# bike-computer.net
KiCad netlist of a schematic drawn in EAGLE
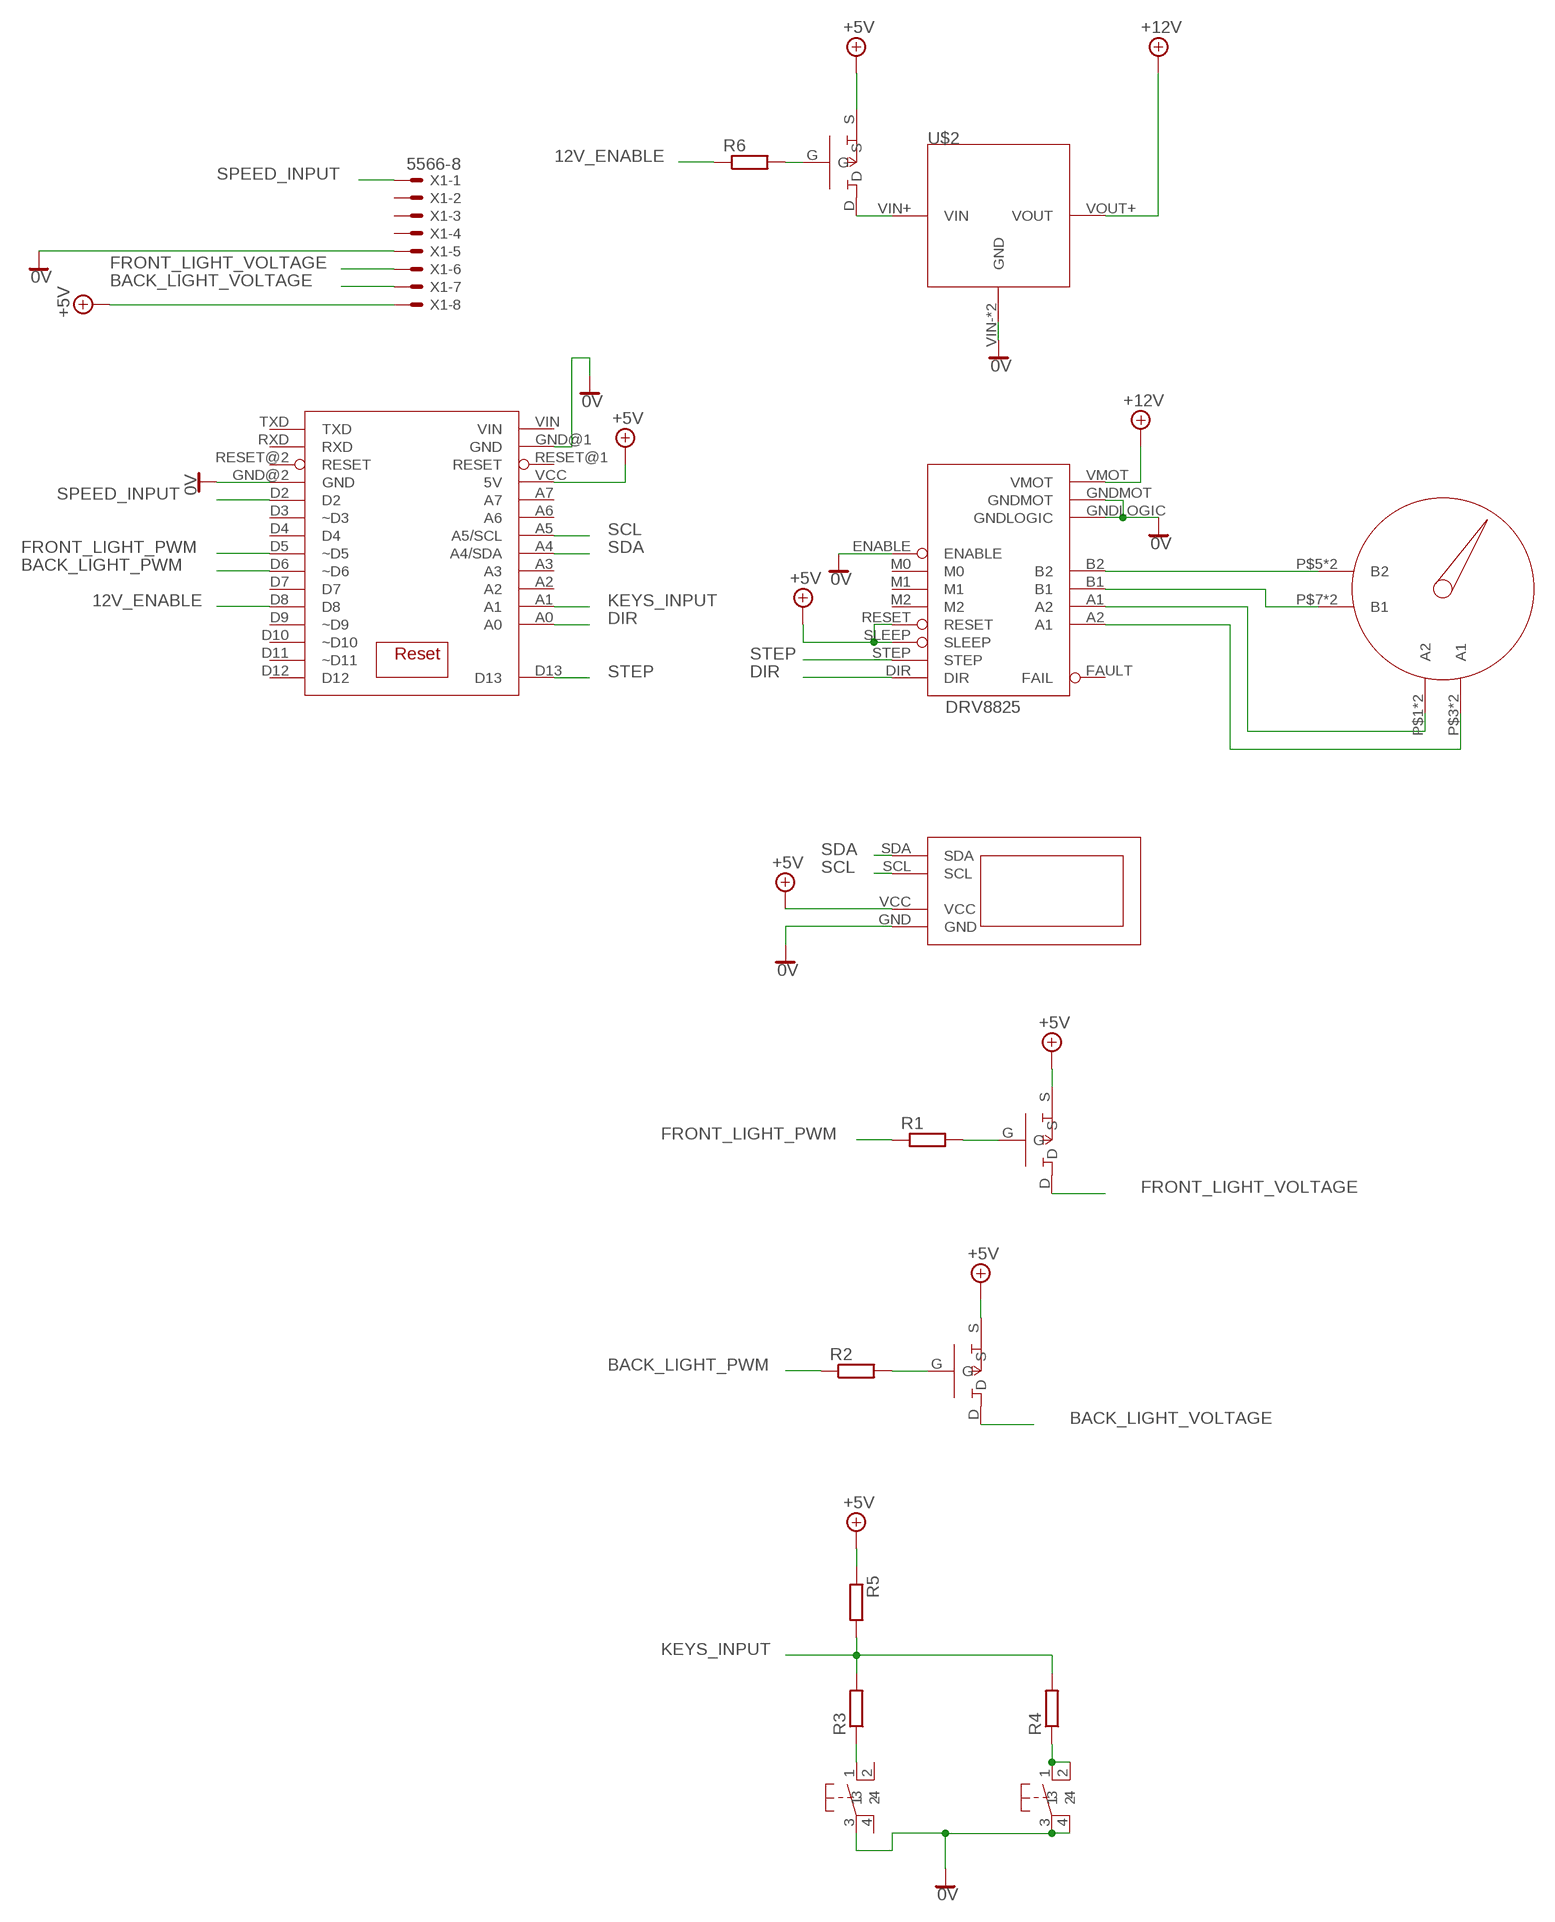
[diagram p0: schematic, sheet 1]

(export (version "E")
  (design (tool "Eeschema 10.0.6"))
  (components
    (comp (ref "DRV8825")
      (value "DRV8825_BOARD")
      (footprint "eagle-import:DRV8255_BOARD")
      (libsource (lib "eagle-import") (part "DRV8825_BOARD"))
    )
    (comp (ref "R1")
      (value "R-EU_0617/17")
      (footprint "eagle-import:0617_17")
      (libsource (lib "eagle-import") (part "R-EU_0617/17"))
    )
    (comp (ref "R2")
      (value "R-EU_0207/15")
      (footprint "eagle-import:0207_15")
      (libsource (lib "eagle-import") (part "R-EU_0207/15"))
    )
    (comp (ref "R3")
      (value "R-EU_0207/12")
      (footprint "eagle-import:0207_12")
      (libsource (lib "eagle-import") (part "R-EU_0207/12"))
    )
    (comp (ref "R4")
      (value "R-EU_0204/5")
      (footprint "eagle-import:0204_5")
      (libsource (lib "eagle-import") (part "R-EU_0204/5"))
    )
    (comp (ref "R5")
      (value "R-EU_0204/5")
      (footprint "eagle-import:0204_5")
      (libsource (lib "eagle-import") (part "R-EU_0204/5"))
    )
    (comp (ref "R6")
      (value "R-EU_0207/15")
      (footprint "eagle-import:0207_15")
      (libsource (lib "eagle-import") (part "R-EU_0207/15"))
    )
    (comp (ref "U$1")
      (value "STEPPER_GAUGE")
      (footprint "eagle-import:STEPPER_GAUGE")
      (libsource (lib "eagle-import") (part "STEPPER_GAUGE"))
    )
    (comp (ref "U$2")
      (value "STEP_UP_REG")
      (footprint "eagle-import:STEP_UP_REG")
      (libsource (lib "eagle-import") (part "STEP_UP_REG"))
    )
    (comp (ref "U$3")
      (value "OLED_0.9")
      (footprint "eagle-import:OLED_0.9")
      (libsource (lib "eagle-import") (part "OLED_0.9"))
    )
    (comp (ref "U$4")
      (value "BS250")
      (footprint "eagle-import:TO92(2.54)")
      (libsource (lib "eagle-import") (part "BS250"))
    )
    (comp (ref "U$5")
      (value "BS250")
      (footprint "eagle-import:TO92(2.54)")
      (libsource (lib "eagle-import") (part "BS250"))
    )
    (comp (ref "U$6")
      (value "BS250")
      (footprint "eagle-import:TO92(2.54)")
      (libsource (lib "eagle-import") (part "BS250"))
    )
    (comp (ref "U$7")
      (value "ARDUINO_PRO_MINI")
      (footprint "eagle-import:ARDUINO_PRO_MINI")
      (libsource (lib "eagle-import") (part "ARDUINO_PRO_MINI"))
    )
    (comp (ref "U$8")
      (value "MICRO_SWITCH")
      (footprint "eagle-import:MICRO_SWITCH")
      (libsource (lib "eagle-import") (part "MICRO_SWITCH"))
    )
    (comp (ref "U$9")
      (value "MICRO_SWITCH")
      (footprint "eagle-import:MICRO_SWITCH")
      (libsource (lib "eagle-import") (part "MICRO_SWITCH"))
    )
    (comp (ref "X1")
      (value "5566-8")
      (footprint "eagle-import:5566-8")
      (fields (field (name "MF") "MOLEX"))
      (libsource (lib "eagle-import") (part "5566-8"))
    )
  )
  (nets
    (net (code "1") (name "+5V") (class "Default")
      (node (ref "DRV8825") (pin "RESET") (pinfunction "RESET_RESET") (pintype "bidirectional"))
      (node (ref "DRV8825") (pin "SLEEP") (pinfunction "SLEEP_SLEEP") (pintype "bidirectional"))
      (node (ref "R5") (pin "1") (pinfunction "1_1") (pintype "passive"))
      (node (ref "U$3") (pin "VCC") (pinfunction "VCC_VCC") (pintype "bidirectional"))
      (node (ref "U$4") (pin "S") (pinfunction "S_S") (pintype "bidirectional"))
      (node (ref "U$5") (pin "S") (pinfunction "S_S") (pintype "bidirectional"))
      (node (ref "U$6") (pin "S") (pinfunction "S_S") (pintype "bidirectional"))
      (node (ref "U$7") (pin "VCC") (pinfunction "5V_VCC") (pintype "bidirectional"))
      (node (ref "X1") (pin "8") (pinfunction "S_8") (pintype "passive"))
    )
    (net (code "2") (name "+12V") (class "Default")
      (node (ref "DRV8825") (pin "VMOT") (pinfunction "VMOT_VMOT") (pintype "bidirectional"))
      (node (ref "U$2") (pin "VOUT+") (pinfunction "VOUT_VOUT+") (pintype "bidirectional"))
    )
    (net (code "3") (name "/12V_ENABLE") (class "Default")
      (node (ref "R6") (pin "1") (pinfunction "1_1") (pintype "passive"))
      (node (ref "U$7") (pin "D8") (pinfunction "D8_D8") (pintype "bidirectional"))
    )
    (net (code "4") (name "/BACK_LIGHT_PWM") (class "Default")
      (node (ref "R2") (pin "1") (pinfunction "1_1") (pintype "passive"))
      (node (ref "U$7") (pin "D6") (pinfunction "~{D6}_D6") (pintype "bidirectional"))
    )
    (net (code "5") (name "/BACK_LIGHT_VOLTAGE") (class "Default")
      (node (ref "U$5") (pin "D") (pinfunction "D_D") (pintype "bidirectional"))
      (node (ref "X1") (pin "7") (pinfunction "S_7") (pintype "passive"))
    )
    (net (code "6") (name "/DIR") (class "Default")
      (node (ref "DRV8825") (pin "DIR") (pinfunction "DIR_DIR") (pintype "bidirectional"))
      (node (ref "U$7") (pin "A0") (pinfunction "A0_A0") (pintype "bidirectional"))
    )
    (net (code "7") (name "/FRONT_LIGHT_PWM") (class "Default")
      (node (ref "R1") (pin "1") (pinfunction "1_1") (pintype "passive"))
      (node (ref "U$7") (pin "D5") (pinfunction "~{D5}_D5") (pintype "bidirectional"))
    )
    (net (code "8") (name "/FRONT_LIGHT_VOLTAGE") (class "Default")
      (node (ref "U$4") (pin "D") (pinfunction "D_D") (pintype "bidirectional"))
      (node (ref "X1") (pin "6") (pinfunction "S_6") (pintype "passive"))
    )
    (net (code "9") (name "/KEYS_INPUT") (class "Default")
      (node (ref "R3") (pin "2") (pinfunction "2_2") (pintype "passive"))
      (node (ref "R4") (pin "2") (pinfunction "2_2") (pintype "passive"))
      (node (ref "R5") (pin "2") (pinfunction "2_2") (pintype "passive"))
      (node (ref "U$7") (pin "A1") (pinfunction "A1_A1") (pintype "bidirectional"))
    )
    (net (code "10") (name "/SCL") (class "Default")
      (node (ref "U$3") (pin "SCL") (pinfunction "SCL_SCL") (pintype "bidirectional"))
      (node (ref "U$7") (pin "A5") (pinfunction "A5/SCL_A5") (pintype "bidirectional"))
    )
    (net (code "11") (name "/SDA") (class "Default")
      (node (ref "U$3") (pin "SDA") (pinfunction "SDA_SDA") (pintype "bidirectional"))
      (node (ref "U$7") (pin "A4") (pinfunction "A4/SDA_A4") (pintype "bidirectional"))
    )
    (net (code "12") (name "/SPEED_INPUT") (class "Default")
      (node (ref "U$7") (pin "D2") (pinfunction "D2_D2") (pintype "bidirectional"))
      (node (ref "X1") (pin "1") (pinfunction "S_1") (pintype "passive"))
    )
    (net (code "13") (name "/STEP") (class "Default")
      (node (ref "DRV8825") (pin "STEP") (pinfunction "STEP_STEP") (pintype "bidirectional"))
      (node (ref "U$7") (pin "D13") (pinfunction "D13_D13") (pintype "bidirectional"))
    )
    (net (code "14") (name "0V") (class "Default")
      (node (ref "DRV8825") (pin "ENABLE") (pinfunction "ENABLE_ENABLE") (pintype "bidirectional"))
      (node (ref "DRV8825") (pin "GNDLOGIC") (pinfunction "GNDLOGIC_GNDLOGIC") (pintype "bidirectional"))
      (node (ref "DRV8825") (pin "GNDMOT") (pinfunction "GNDMOT_GNDMOT") (pintype "bidirectional"))
      (node (ref "U$2") (pin "VIN-") (pinfunction "GND_VIN-") (pintype "bidirectional"))
      (node (ref "U$2") (pin "VOUT-") (pinfunction "GND_VOUT-") (pintype "bidirectional"))
      (node (ref "U$3") (pin "GND") (pinfunction "GND_GND") (pintype "bidirectional"))
      (node (ref "U$7") (pin "GND@1") (pinfunction "GND_GND@1") (pintype "bidirectional"))
      (node (ref "U$7") (pin "GND@2") (pinfunction "GND_GND@2") (pintype "bidirectional"))
      (node (ref "U$8") (pin "3") (pinfunction "3_3") (pintype "bidirectional"))
      (node (ref "U$9") (pin "3") (pinfunction "3_3") (pintype "bidirectional"))
      (node (ref "U$9") (pin "4") (pinfunction "4_4") (pintype "bidirectional"))
      (node (ref "X1") (pin "5") (pinfunction "S_5") (pintype "passive"))
    )
    (net (code "15") (name "Net-(DRV8825-A1)") (class "Default")
      (node (ref "DRV8825") (pin "A2") (pinfunction "A1_A2") (pintype "output"))
      (node (ref "U$1") (pin "P$3") (pinfunction "A1_P$3") (pintype "bidirectional"))
      (node (ref "U$1") (pin "P$4") (pinfunction "A1_P$4") (pintype "bidirectional"))
    )
    (net (code "16") (name "Net-(DRV8825-A2)") (class "Default")
      (node (ref "DRV8825") (pin "A1") (pinfunction "A2_A1") (pintype "output"))
      (node (ref "U$1") (pin "P$1") (pinfunction "A2_P$1") (pintype "bidirectional"))
      (node (ref "U$1") (pin "P$2") (pinfunction "A2_P$2") (pintype "bidirectional"))
    )
    (net (code "17") (name "Net-(DRV8825-PadB1)") (class "Default")
      (node (ref "DRV8825") (pin "B1") (pinfunction "B1_B1") (pintype "output"))
      (node (ref "U$1") (pin "P$7") (pinfunction "B1_P$7") (pintype "bidirectional"))
      (node (ref "U$1") (pin "P$8") (pinfunction "B1_P$8") (pintype "bidirectional"))
    )
    (net (code "18") (name "Net-(DRV8825-PadB2)") (class "Default")
      (node (ref "DRV8825") (pin "B2") (pinfunction "B2_B2") (pintype "output"))
      (node (ref "U$1") (pin "P$5") (pinfunction "B2_P$5") (pintype "bidirectional"))
      (node (ref "U$1") (pin "P$6") (pinfunction "B2_P$6") (pintype "bidirectional"))
    )
    (net (code "19") (name "Net-(R1-Pad2)") (class "Default")
      (node (ref "R1") (pin "2") (pinfunction "2_2") (pintype "passive"))
      (node (ref "U$4") (pin "G") (pinfunction "G_G") (pintype "bidirectional"))
    )
    (net (code "20") (name "Net-(R2-Pad2)") (class "Default")
      (node (ref "R2") (pin "2") (pinfunction "2_2") (pintype "passive"))
      (node (ref "U$5") (pin "G") (pinfunction "G_G") (pintype "bidirectional"))
    )
    (net (code "21") (name "Net-(R3-Pad1)") (class "Default")
      (node (ref "R3") (pin "1") (pinfunction "1_1") (pintype "passive"))
      (node (ref "U$8") (pin "1") (pinfunction "1_1") (pintype "bidirectional"))
    )
    (net (code "22") (name "Net-(R4-Pad1)") (class "Default")
      (node (ref "R4") (pin "1") (pinfunction "1_1") (pintype "passive"))
      (node (ref "U$9") (pin "1") (pinfunction "1_1") (pintype "bidirectional"))
      (node (ref "U$9") (pin "2") (pinfunction "2_2") (pintype "bidirectional"))
    )
    (net (code "23") (name "Net-(R6-Pad2)") (class "Default")
      (node (ref "R6") (pin "2") (pinfunction "2_2") (pintype "passive"))
      (node (ref "U$6") (pin "G") (pinfunction "G_G") (pintype "bidirectional"))
    )
    (net (code "24") (name "Net-(U$2-VIN)") (class "Default")
      (node (ref "U$2") (pin "VIN+") (pinfunction "VIN_VIN+") (pintype "bidirectional"))
      (node (ref "U$6") (pin "D") (pinfunction "D_D") (pintype "bidirectional"))
    )
    (net (code "25") (name "unconnected-(DRV8825-FAIL-PadFAULT)") (class "Default")
      (node (ref "DRV8825") (pin "FAULT") (pinfunction "FAIL_FAULT") (pintype "output"))
    )
    (net (code "26") (name "unconnected-(DRV8825-PadM0)") (class "Default")
      (node (ref "DRV8825") (pin "M0") (pinfunction "M0_M0") (pintype "input"))
    )
    (net (code "27") (name "unconnected-(DRV8825-PadM1)") (class "Default")
      (node (ref "DRV8825") (pin "M1") (pinfunction "M1_M1") (pintype "bidirectional"))
    )
    (net (code "28") (name "unconnected-(DRV8825-PadM2)") (class "Default")
      (node (ref "DRV8825") (pin "M2") (pinfunction "M2_M2") (pintype "bidirectional"))
    )
    (net (code "29") (name "unconnected-(U$7-PadA2)") (class "Default")
      (node (ref "U$7") (pin "A2") (pinfunction "A2_A2") (pintype "bidirectional"))
    )
    (net (code "30") (name "unconnected-(U$7-PadA3)") (class "Default")
      (node (ref "U$7") (pin "A3") (pinfunction "A3_A3") (pintype "bidirectional"))
    )
    (net (code "31") (name "unconnected-(U$7-PadA6)") (class "Default")
      (node (ref "U$7") (pin "A6") (pinfunction "A6_A6") (pintype "bidirectional"))
    )
    (net (code "32") (name "unconnected-(U$7-PadA7)") (class "Default")
      (node (ref "U$7") (pin "A7") (pinfunction "A7_A7") (pintype "bidirectional"))
    )
    (net (code "33") (name "unconnected-(U$7-PadD4)") (class "Default")
      (node (ref "U$7") (pin "D4") (pinfunction "D4_D4") (pintype "bidirectional"))
    )
    (net (code "34") (name "unconnected-(U$7-PadD7)") (class "Default")
      (node (ref "U$7") (pin "D7") (pinfunction "D7_D7") (pintype "bidirectional"))
    )
    (net (code "35") (name "unconnected-(U$7-PadD12)") (class "Default")
      (node (ref "U$7") (pin "D12") (pinfunction "D12_D12") (pintype "bidirectional"))
    )
    (net (code "36") (name "unconnected-(U$7-PadRXD)") (class "Default")
      (node (ref "U$7") (pin "RXD") (pinfunction "RXD_RXD") (pintype "bidirectional"))
    )
    (net (code "37") (name "unconnected-(U$7-PadTXD)") (class "Default")
      (node (ref "U$7") (pin "TXD") (pinfunction "TXD_TXD") (pintype "bidirectional"))
    )
    (net (code "38") (name "unconnected-(U$7-PadVIN)") (class "Default")
      (node (ref "U$7") (pin "VIN") (pinfunction "VIN_VIN") (pintype "bidirectional"))
    )
    (net (code "39") (name "unconnected-(U$7-RESET-PadRESET@1)") (class "Default")
      (node (ref "U$7") (pin "RESET@1") (pinfunction "RESET_RESET@1") (pintype "bidirectional"))
    )
    (net (code "40") (name "unconnected-(U$7-RESET-PadRESET@2)") (class "Default")
      (node (ref "U$7") (pin "RESET@2") (pinfunction "RESET_RESET@2") (pintype "bidirectional"))
    )
    (net (code "41") (name "unconnected-(U$7-~{D3}-PadD3)") (class "Default")
      (node (ref "U$7") (pin "D3") (pinfunction "~{D3}_D3") (pintype "bidirectional"))
    )
    (net (code "42") (name "unconnected-(U$7-~{D9}-PadD9)") (class "Default")
      (node (ref "U$7") (pin "D9") (pinfunction "~{D9}_D9") (pintype "bidirectional"))
    )
    (net (code "43") (name "unconnected-(U$7-~{D10}-PadD10)") (class "Default")
      (node (ref "U$7") (pin "D10") (pinfunction "~{D10}_D10") (pintype "bidirectional"))
    )
    (net (code "44") (name "unconnected-(U$7-~{D11}-PadD11)") (class "Default")
      (node (ref "U$7") (pin "D11") (pinfunction "~{D11}_D11") (pintype "bidirectional"))
    )
    (net (code "45") (name "unconnected-(U$8-Pad2)") (class "Default")
      (node (ref "U$8") (pin "2") (pinfunction "2_2") (pintype "bidirectional"))
    )
    (net (code "46") (name "unconnected-(U$8-Pad4)") (class "Default")
      (node (ref "U$8") (pin "4") (pinfunction "4_4") (pintype "bidirectional"))
    )
    (net (code "47") (name "unconnected-(X1B-S-Pad2)") (class "Default")
      (node (ref "X1") (pin "2") (pinfunction "S_2") (pintype "passive"))
    )
    (net (code "48") (name "unconnected-(X1C-S-Pad3)") (class "Default")
      (node (ref "X1") (pin "3") (pinfunction "S_3") (pintype "passive"))
    )
    (net (code "49") (name "unconnected-(X1D-S-Pad4)") (class "Default")
      (node (ref "X1") (pin "4") (pinfunction "S_4") (pintype "passive"))
    )
  )
)
